# modFOC-GateDrivers.net
KiCad netlist of a schematic drawn in Altium Designer
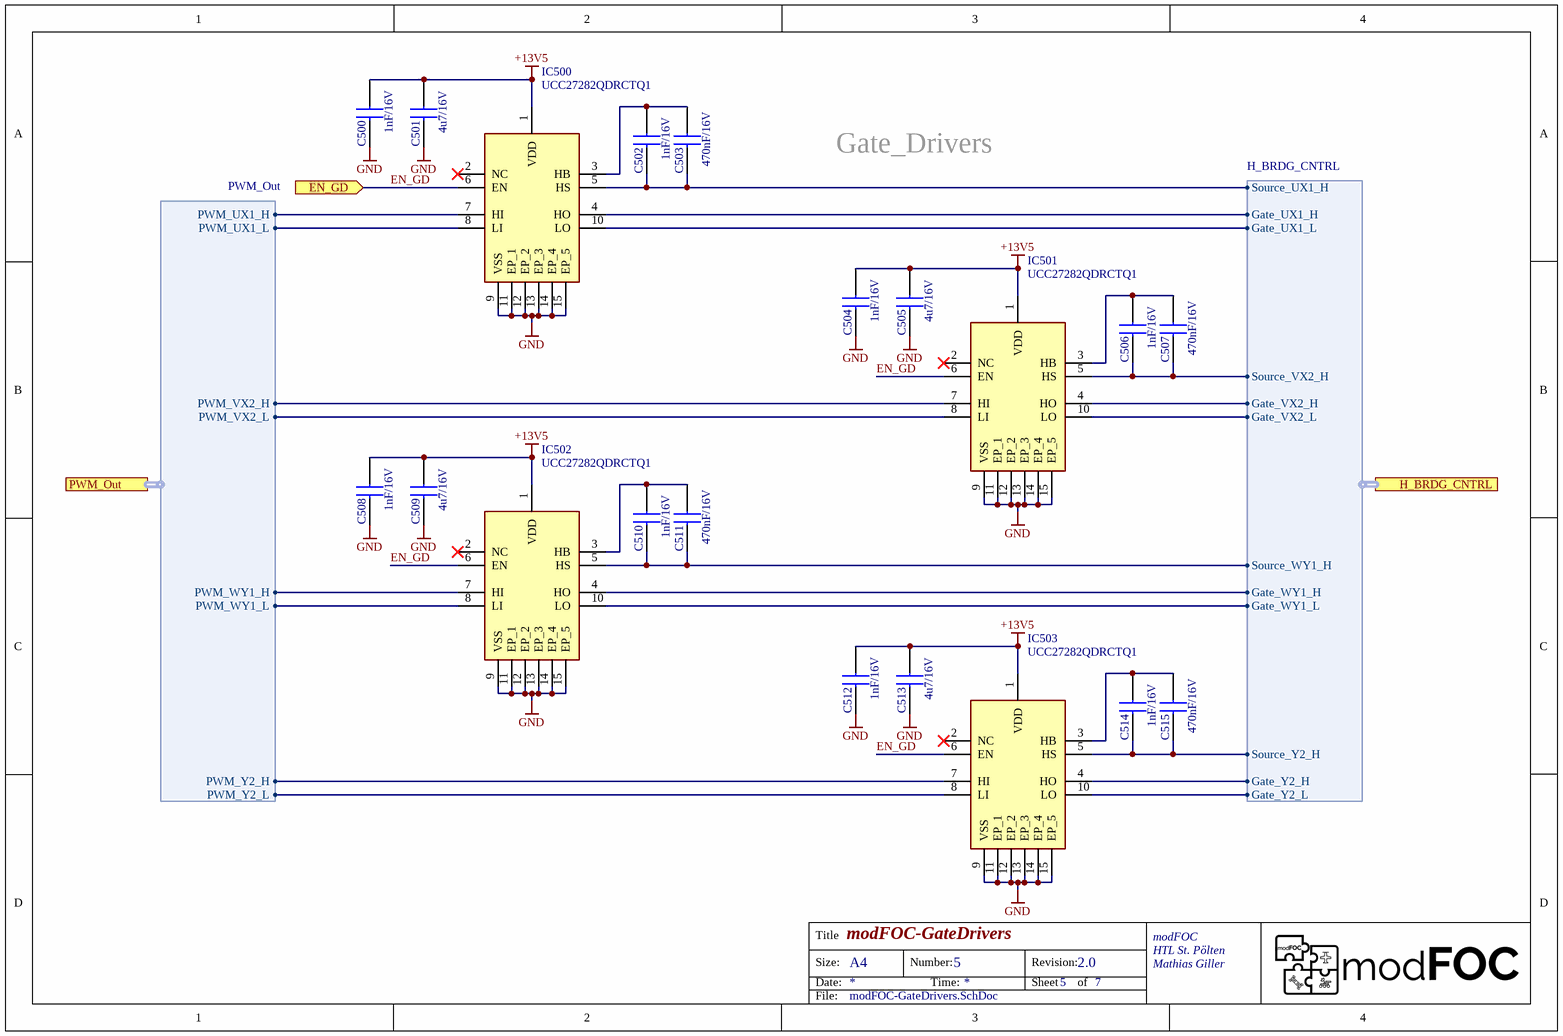
[diagram p0: modFOC-GateDrivers.SchDoc]

(export (version "E")
  (design (tool "Eeschema 10.0.6"))
  (components
    (comp (ref "C500")
      (value "1nF/16V")
      (footprint "CAPC1608X97N")
      (description "Capacitor")
      (libsource (lib "Schlib1") (part "C0603"))
    )
    (comp (ref "C501")
      (value "4u7/16V")
      (footprint "CAPC1608X97N")
      (description "Capacitor")
      (libsource (lib "Schlib1") (part "C0603"))
    )
    (comp (ref "C502")
      (value "1nF/16V")
      (footprint "CAPC1608X97N")
      (description "Capacitor")
      (libsource (lib "Schlib1") (part "C0603"))
    )
    (comp (ref "C503")
      (value "470nF/16V")
      (footprint "CAPC1608X97N")
      (description "Capacitor")
      (libsource (lib "Schlib1") (part "C0603"))
    )
    (comp (ref "C504")
      (value "1nF/16V")
      (footprint "CAPC1608X97N")
      (description "Capacitor")
      (libsource (lib "Schlib1") (part "C0603"))
    )
    (comp (ref "C505")
      (value "4u7/16V")
      (footprint "CAPC1608X97N")
      (description "Capacitor")
      (libsource (lib "Schlib1") (part "C0603"))
    )
    (comp (ref "C506")
      (value "1nF/16V")
      (footprint "CAPC1608X97N")
      (description "Capacitor")
      (libsource (lib "Schlib1") (part "C0603"))
    )
    (comp (ref "C507")
      (value "470nF/16V")
      (footprint "CAPC1608X97N")
      (description "Capacitor")
      (libsource (lib "Schlib1") (part "C0603"))
    )
    (comp (ref "C508")
      (value "1nF/16V")
      (footprint "CAPC1608X97N")
      (description "Capacitor")
      (libsource (lib "Schlib1") (part "C0603"))
    )
    (comp (ref "C509")
      (value "4u7/16V")
      (footprint "CAPC1608X97N")
      (description "Capacitor")
      (libsource (lib "Schlib1") (part "C0603"))
    )
    (comp (ref "C510")
      (value "1nF/16V")
      (footprint "CAPC1608X97N")
      (description "Capacitor")
      (libsource (lib "Schlib1") (part "C0603"))
    )
    (comp (ref "C511")
      (value "470nF/16V")
      (footprint "CAPC1608X97N")
      (description "Capacitor")
      (libsource (lib "Schlib1") (part "C0603"))
    )
    (comp (ref "C512")
      (value "1nF/16V")
      (footprint "CAPC1608X97N")
      (description "Capacitor")
      (libsource (lib "Schlib1") (part "C0603"))
    )
    (comp (ref "C513")
      (value "4u7/16V")
      (footprint "CAPC1608X97N")
      (description "Capacitor")
      (libsource (lib "Schlib1") (part "C0603"))
    )
    (comp (ref "C514")
      (value "1nF/16V")
      (footprint "CAPC1608X97N")
      (description "Capacitor")
      (libsource (lib "Schlib1") (part "C0603"))
    )
    (comp (ref "C515")
      (value "470nF/16V")
      (footprint "CAPC1608X97N")
      (description "Capacitor")
      (libsource (lib "Schlib1") (part "C0603"))
    )
    (comp (ref "IC500")
      (value "UCC27282QDRCTQ1")
      (footprint "UCC27282DRCR")
      (description "Halfbridge driver IC")
      (fields
        (field (name "MOUSER PART NUMBER") "595-UCC27282DRCR")
        (field (name "ARROW PART NUMBER") "UCC27282DRCR")
      )
      (libsource (lib "Schlib1") (part "UCC27282QDRCTQ1"))
    )
    (comp (ref "IC501")
      (value "UCC27282QDRCTQ1")
      (footprint "UCC27282DRCR")
      (description "Halfbridge driver IC")
      (fields
        (field (name "MOUSER PART NUMBER") "595-UCC27282DRCR")
        (field (name "ARROW PART NUMBER") "UCC27282DRCR")
      )
      (libsource (lib "Schlib1") (part "UCC27282QDRCTQ1"))
    )
    (comp (ref "IC502")
      (value "UCC27282QDRCTQ1")
      (footprint "UCC27282DRCR")
      (description "Halfbridge driver IC")
      (fields
        (field (name "MOUSER PART NUMBER") "595-UCC27282DRCR")
        (field (name "ARROW PART NUMBER") "UCC27282DRCR")
      )
      (libsource (lib "Schlib1") (part "UCC27282QDRCTQ1"))
    )
    (comp (ref "IC503")
      (value "UCC27282QDRCTQ1")
      (footprint "UCC27282DRCR")
      (description "Halfbridge driver IC")
      (fields
        (field (name "MOUSER PART NUMBER") "595-UCC27282DRCR")
        (field (name "ARROW PART NUMBER") "UCC27282DRCR")
      )
      (libsource (lib "Schlib1") (part "UCC27282QDRCTQ1"))
    )
  )
  (nets
    (net (code "3") (name "+13V5") (class "Default")
      (node (ref "C500") (pin "2") (pinfunction "2_2") (pintype "passive"))
      (node (ref "C501") (pin "2") (pinfunction "2_2") (pintype "passive"))
      (node (ref "C504") (pin "2") (pinfunction "2_2") (pintype "passive"))
      (node (ref "C505") (pin "2") (pinfunction "2_2") (pintype "passive"))
      (node (ref "C508") (pin "2") (pinfunction "2_2") (pintype "passive"))
      (node (ref "C509") (pin "2") (pinfunction "2_2") (pintype "passive"))
      (node (ref "C512") (pin "2") (pinfunction "2_2") (pintype "passive"))
      (node (ref "C513") (pin "2") (pinfunction "2_2") (pintype "passive"))
      (node (ref "IC500") (pin "1") (pinfunction "VDD_1") (pintype "passive"))
      (node (ref "IC501") (pin "1") (pinfunction "VDD_1") (pintype "passive"))
      (node (ref "IC502") (pin "1") (pinfunction "VDD_1") (pintype "passive"))
      (node (ref "IC503") (pin "1") (pinfunction "VDD_1") (pintype "passive"))
    )
    (net (code "4") (name "/EN_GD") (class "Default")
      (node (ref "IC500") (pin "6") (pinfunction "EN_6") (pintype "passive"))
      (node (ref "IC501") (pin "6") (pinfunction "EN_6") (pintype "passive"))
      (node (ref "IC502") (pin "6") (pinfunction "EN_6") (pintype "passive"))
      (node (ref "IC503") (pin "6") (pinfunction "EN_6") (pintype "passive"))
    )
    (net (code "5") (name "/Gate_UX1_H") (class "Default")
      (node (ref "IC500") (pin "4") (pinfunction "HO_4") (pintype "passive"))
    )
    (net (code "6") (name "/Gate_UX1_L") (class "Default")
      (node (ref "IC500") (pin "10") (pinfunction "LO_10") (pintype "passive"))
    )
    (net (code "7") (name "/Gate_VX2_H") (class "Default")
      (node (ref "IC501") (pin "4") (pinfunction "HO_4") (pintype "passive"))
    )
    (net (code "8") (name "/Gate_VX2_L") (class "Default")
      (node (ref "IC501") (pin "10") (pinfunction "LO_10") (pintype "passive"))
    )
    (net (code "9") (name "/Gate_WY1_H") (class "Default")
      (node (ref "IC502") (pin "4") (pinfunction "HO_4") (pintype "passive"))
    )
    (net (code "10") (name "/Gate_WY1_L") (class "Default")
      (node (ref "IC502") (pin "10") (pinfunction "LO_10") (pintype "passive"))
    )
    (net (code "11") (name "/Gate_Y2_H") (class "Default")
      (node (ref "IC503") (pin "4") (pinfunction "HO_4") (pintype "passive"))
    )
    (net (code "12") (name "/Gate_Y2_L") (class "Default")
      (node (ref "IC503") (pin "10") (pinfunction "LO_10") (pintype "passive"))
    )
    (net (code "13") (name "/PWM_UX1_H") (class "Default")
      (node (ref "IC500") (pin "7") (pinfunction "HI_7") (pintype "passive"))
    )
    (net (code "14") (name "/PWM_UX1_L") (class "Default")
      (node (ref "IC500") (pin "8") (pinfunction "LI_8") (pintype "passive"))
    )
    (net (code "15") (name "/PWM_VX2_H") (class "Default")
      (node (ref "IC501") (pin "7") (pinfunction "HI_7") (pintype "passive"))
    )
    (net (code "16") (name "/PWM_VX2_L") (class "Default")
      (node (ref "IC501") (pin "8") (pinfunction "LI_8") (pintype "passive"))
    )
    (net (code "17") (name "/PWM_WY1_H") (class "Default")
      (node (ref "IC502") (pin "7") (pinfunction "HI_7") (pintype "passive"))
    )
    (net (code "18") (name "/PWM_WY1_L") (class "Default")
      (node (ref "IC502") (pin "8") (pinfunction "LI_8") (pintype "passive"))
    )
    (net (code "19") (name "/PWM_Y2_H") (class "Default")
      (node (ref "IC503") (pin "7") (pinfunction "HI_7") (pintype "passive"))
    )
    (net (code "20") (name "/PWM_Y2_L") (class "Default")
      (node (ref "IC503") (pin "8") (pinfunction "LI_8") (pintype "passive"))
    )
    (net (code "21") (name "/Source_UX1_H") (class "Default")
      (node (ref "C502") (pin "1") (pinfunction "1_1") (pintype "passive"))
      (node (ref "C503") (pin "1") (pinfunction "1_1") (pintype "passive"))
      (node (ref "IC500") (pin "5") (pinfunction "HS_5") (pintype "passive"))
    )
    (net (code "22") (name "/Source_VX2_H") (class "Default")
      (node (ref "C506") (pin "1") (pinfunction "1_1") (pintype "passive"))
      (node (ref "C507") (pin "1") (pinfunction "1_1") (pintype "passive"))
      (node (ref "IC501") (pin "5") (pinfunction "HS_5") (pintype "passive"))
    )
    (net (code "23") (name "/Source_WY1_H") (class "Default")
      (node (ref "C510") (pin "1") (pinfunction "1_1") (pintype "passive"))
      (node (ref "C511") (pin "1") (pinfunction "1_1") (pintype "passive"))
      (node (ref "IC502") (pin "5") (pinfunction "HS_5") (pintype "passive"))
    )
    (net (code "24") (name "/Source_Y2_H") (class "Default")
      (node (ref "C514") (pin "1") (pinfunction "1_1") (pintype "passive"))
      (node (ref "C515") (pin "1") (pinfunction "1_1") (pintype "passive"))
      (node (ref "IC503") (pin "5") (pinfunction "HS_5") (pintype "passive"))
    )
    (net (code "27") (name "GND") (class "Default")
      (node (ref "C500") (pin "1") (pinfunction "1_1") (pintype "passive"))
      (node (ref "C501") (pin "1") (pinfunction "1_1") (pintype "passive"))
      (node (ref "C504") (pin "1") (pinfunction "1_1") (pintype "passive"))
      (node (ref "C505") (pin "1") (pinfunction "1_1") (pintype "passive"))
      (node (ref "C508") (pin "1") (pinfunction "1_1") (pintype "passive"))
      (node (ref "C509") (pin "1") (pinfunction "1_1") (pintype "passive"))
      (node (ref "C512") (pin "1") (pinfunction "1_1") (pintype "passive"))
      (node (ref "C513") (pin "1") (pinfunction "1_1") (pintype "passive"))
      (node (ref "IC500") (pin "11") (pinfunction "EP_1_11") (pintype "passive"))
      (node (ref "IC500") (pin "12") (pinfunction "EP_2_12") (pintype "passive"))
      (node (ref "IC500") (pin "13") (pinfunction "EP_3_13") (pintype "passive"))
      (node (ref "IC500") (pin "14") (pinfunction "EP_4_14") (pintype "passive"))
      (node (ref "IC500") (pin "15") (pinfunction "EP_5_15") (pintype "passive"))
      (node (ref "IC500") (pin "9") (pinfunction "VSS_9") (pintype "passive"))
      (node (ref "IC501") (pin "11") (pinfunction "EP_1_11") (pintype "passive"))
      (node (ref "IC501") (pin "12") (pinfunction "EP_2_12") (pintype "passive"))
      (node (ref "IC501") (pin "13") (pinfunction "EP_3_13") (pintype "passive"))
      (node (ref "IC501") (pin "14") (pinfunction "EP_4_14") (pintype "passive"))
      (node (ref "IC501") (pin "15") (pinfunction "EP_5_15") (pintype "passive"))
      (node (ref "IC501") (pin "9") (pinfunction "VSS_9") (pintype "passive"))
      (node (ref "IC502") (pin "11") (pinfunction "EP_1_11") (pintype "passive"))
      (node (ref "IC502") (pin "12") (pinfunction "EP_2_12") (pintype "passive"))
      (node (ref "IC502") (pin "13") (pinfunction "EP_3_13") (pintype "passive"))
      (node (ref "IC502") (pin "14") (pinfunction "EP_4_14") (pintype "passive"))
      (node (ref "IC502") (pin "15") (pinfunction "EP_5_15") (pintype "passive"))
      (node (ref "IC502") (pin "9") (pinfunction "VSS_9") (pintype "passive"))
      (node (ref "IC503") (pin "11") (pinfunction "EP_1_11") (pintype "passive"))
      (node (ref "IC503") (pin "12") (pinfunction "EP_2_12") (pintype "passive"))
      (node (ref "IC503") (pin "13") (pinfunction "EP_3_13") (pintype "passive"))
      (node (ref "IC503") (pin "14") (pinfunction "EP_4_14") (pintype "passive"))
      (node (ref "IC503") (pin "15") (pinfunction "EP_5_15") (pintype "passive"))
      (node (ref "IC503") (pin "9") (pinfunction "VSS_9") (pintype "passive"))
    )
    (net (code "28") (name "Net-(IC500-HB)") (class "Default")
      (node (ref "C502") (pin "2") (pinfunction "2_2") (pintype "passive"))
      (node (ref "C503") (pin "2") (pinfunction "2_2") (pintype "passive"))
      (node (ref "IC500") (pin "3") (pinfunction "HB_3") (pintype "passive"))
    )
    (net (code "29") (name "Net-(IC501-HB)") (class "Default")
      (node (ref "C506") (pin "2") (pinfunction "2_2") (pintype "passive"))
      (node (ref "C507") (pin "2") (pinfunction "2_2") (pintype "passive"))
      (node (ref "IC501") (pin "3") (pinfunction "HB_3") (pintype "passive"))
    )
    (net (code "30") (name "Net-(IC502-HB)") (class "Default")
      (node (ref "C510") (pin "2") (pinfunction "2_2") (pintype "passive"))
      (node (ref "C511") (pin "2") (pinfunction "2_2") (pintype "passive"))
      (node (ref "IC502") (pin "3") (pinfunction "HB_3") (pintype "passive"))
    )
    (net (code "31") (name "Net-(IC503-HB)") (class "Default")
      (node (ref "C514") (pin "2") (pinfunction "2_2") (pintype "passive"))
      (node (ref "C515") (pin "2") (pinfunction "2_2") (pintype "passive"))
      (node (ref "IC503") (pin "3") (pinfunction "HB_3") (pintype "passive"))
    )
    (net (code "32") (name "unconnected-(IC500-NC-Pad2)") (class "Default")
      (node (ref "IC500") (pin "2") (pinfunction "NC_2") (pintype "passive+no_connect"))
    )
    (net (code "33") (name "unconnected-(IC501-NC-Pad2)") (class "Default")
      (node (ref "IC501") (pin "2") (pinfunction "NC_2") (pintype "passive+no_connect"))
    )
    (net (code "34") (name "unconnected-(IC502-NC-Pad2)") (class "Default")
      (node (ref "IC502") (pin "2") (pinfunction "NC_2") (pintype "passive+no_connect"))
    )
    (net (code "35") (name "unconnected-(IC503-NC-Pad2)") (class "Default")
      (node (ref "IC503") (pin "2") (pinfunction "NC_2") (pintype "passive+no_connect"))
    )
  )
)
